# 6_Connector.net
KiCad netlist of a schematic drawn in Altium Designer
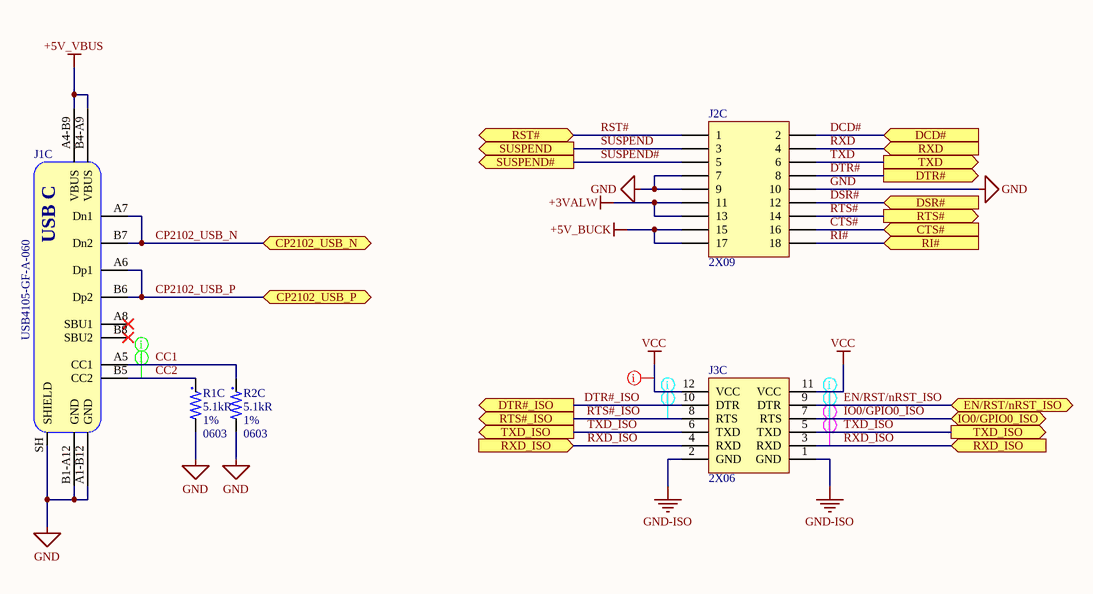
[diagram p0: 6_Connector.SchDoc]

(export (version "E")
  (design (tool "Eeschema 10.0.6"))
  (components
    (comp (ref "J1C")
      (value "USB4105-GF-A-060")
      (footprint "USB-Type-C-16-Pin-SMT")
      (description "USB Connector Type C SMT 16 Pin\r\n(Power pins joints = 12 pins)")
      (fields (field (name "MANUFACTURER") "GCT"))
      (libsource (lib "Lib_Connector") (part "USB-Type-C-16-Pin-SMT"))
    )
    (comp (ref "J2C")
      (value "2X09")
      (footprint "PinHeader_2x09_P2.54mm_Vertical")
      (libsource (lib "Lib_Connector_PinHeader_2.54mm") (part "PinHeader 2X09 DU"))
    )
    (comp (ref "J3C")
      (value "2X06")
      (footprint "PinHeader_2x06_P2.54mm_Vertical")
      (libsource (lib "Lib_Connector_PinHeader_2.54mm") (part "UART_2x06_P2.54mm_V2"))
    )
    (comp (ref "R1C")
      (value "5.1kR")
      (footprint "R0603-MFG")
      (description "SMD Chip Resistor, 5.1 kOhm, ± 1%, 100 mW, 0603 [1608 Metric], Thick Film, General Purpose")
      (fields
        (field (name "MANUFACTURER") "Vishay")
        (field (name "MANUFACTURER PART NUMBER") "CRCW06035K10FKEA")
        (field (name "TOLERANCE") "1%")
        (field (name "CASE/PACKAGE") "0603")
      )
      (libsource (lib "Lib_Register_0603") (part "5.1K"))
    )
    (comp (ref "R2C")
      (value "5.1kR")
      (footprint "R0603-MFG")
      (description "SMD Chip Resistor, 5.1 kOhm, ± 1%, 100 mW, 0603 [1608 Metric], Thick Film, General Purpose")
      (fields
        (field (name "MANUFACTURER") "Vishay")
        (field (name "MANUFACTURER PART NUMBER") "CRCW06035K10FKEA")
        (field (name "TOLERANCE") "1%")
        (field (name "CASE/PACKAGE") "0603")
      )
      (libsource (lib "Lib_Register_0603") (part "5.1K"))
    )
  )
  (nets
    (net (code "1") (name "+3VALW") (class "Default")
      (node (ref "J2C") (pin "11") (pinfunction "11_11") (pintype "passive"))
      (node (ref "J2C") (pin "13") (pinfunction "13_13") (pintype "passive"))
    )
    (net (code "2") (name "+5V_BUCK") (class "Default")
      (node (ref "J2C") (pin "15") (pinfunction "15_15") (pintype "passive"))
      (node (ref "J2C") (pin "17") (pinfunction "17_17") (pintype "passive"))
    )
    (net (code "3") (name "+5V_VBUS") (class "Default")
      (node (ref "J1C") (pin "A4-B9") (pinfunction "VBUS_A4-B9") (pintype "passive"))
      (node (ref "J1C") (pin "B4-A9") (pinfunction "VBUS_B4-A9") (pintype "passive"))
    )
    (net (code "4") (name "/CC1") (class "Default")
      (node (ref "J1C") (pin "A5") (pinfunction "CC1_A5") (pintype "passive"))
      (node (ref "R2C") (pin "1") (pinfunction "1_1") (pintype "passive"))
    )
    (net (code "5") (name "/CC2") (class "Default")
      (node (ref "J1C") (pin "B5") (pinfunction "CC2_B5") (pintype "passive"))
      (node (ref "R1C") (pin "1") (pinfunction "1_1") (pintype "passive"))
    )
    (net (code "6") (name "/CP2102_USB_N") (class "Default")
      (node (ref "J1C") (pin "A7") (pinfunction "Dn1_A7") (pintype "passive"))
      (node (ref "J1C") (pin "B7") (pinfunction "Dn2_B7") (pintype "passive"))
    )
    (net (code "7") (name "/CP2102_USB_P") (class "Default")
      (node (ref "J1C") (pin "A6") (pinfunction "Dp1_A6") (pintype "passive"))
      (node (ref "J1C") (pin "B6") (pinfunction "Dp2_B6") (pintype "passive"))
    )
    (net (code "8") (name "/CTS#") (class "Default")
      (node (ref "J2C") (pin "16") (pinfunction "16_16") (pintype "passive"))
    )
    (net (code "9") (name "/DCD#") (class "Default")
      (node (ref "J2C") (pin "2") (pinfunction "2_2") (pintype "passive"))
    )
    (net (code "10") (name "/DSR#") (class "Default")
      (node (ref "J2C") (pin "12") (pinfunction "12_12") (pintype "passive"))
    )
    (net (code "11") (name "/DTR#") (class "Default")
      (node (ref "J2C") (pin "8") (pinfunction "8_8") (pintype "passive"))
    )
    (net (code "12") (name "/DTR#_ISO") (class "Default")
      (node (ref "J3C") (pin "10") (pinfunction "DTR_10") (pintype "passive"))
    )
    (net (code "13") (name "/EN{slash}RST{slash}nRST_ISO") (class "Default")
      (node (ref "J3C") (pin "9") (pinfunction "DTR_9") (pintype "passive"))
    )
    (net (code "14") (name "/IO0{slash}GPIO0_ISO") (class "Default")
      (node (ref "J3C") (pin "7") (pinfunction "RTS_7") (pintype "passive"))
    )
    (net (code "15") (name "/RI#") (class "Default")
      (node (ref "J2C") (pin "18") (pinfunction "18_18") (pintype "passive"))
    )
    (net (code "16") (name "/RST#") (class "Default")
      (node (ref "J2C") (pin "1") (pinfunction "1_1") (pintype "passive"))
    )
    (net (code "17") (name "/RTS#") (class "Default")
      (node (ref "J2C") (pin "14") (pinfunction "14_14") (pintype "passive"))
    )
    (net (code "18") (name "/RTS#_ISO") (class "Default")
      (node (ref "J3C") (pin "8") (pinfunction "RTS_8") (pintype "passive"))
    )
    (net (code "19") (name "/RXD") (class "Default")
      (node (ref "J2C") (pin "4") (pinfunction "4_4") (pintype "passive"))
    )
    (net (code "20") (name "/RXD_ISO") (class "Default")
      (node (ref "J3C") (pin "3") (pinfunction "RXD_3") (pintype "passive"))
      (node (ref "J3C") (pin "4") (pinfunction "RXD_4") (pintype "passive"))
    )
    (net (code "21") (name "/SUSPEND") (class "Default")
      (node (ref "J2C") (pin "3") (pinfunction "3_3") (pintype "passive"))
    )
    (net (code "22") (name "/SUSPEND#") (class "Default")
      (node (ref "J2C") (pin "5") (pinfunction "5_5") (pintype "passive"))
    )
    (net (code "23") (name "/TXD") (class "Default")
      (node (ref "J2C") (pin "6") (pinfunction "6_6") (pintype "passive"))
    )
    (net (code "24") (name "/TXD_ISO") (class "Default")
      (node (ref "J3C") (pin "5") (pinfunction "TXD_5") (pintype "passive"))
      (node (ref "J3C") (pin "6") (pinfunction "TXD_6") (pintype "passive"))
    )
    (net (code "25") (name "GND") (class "Default")
      (node (ref "J1C") (pin "A1-B12") (pinfunction "GND_A1-B12") (pintype "passive"))
      (node (ref "J1C") (pin "B1-A12") (pinfunction "GND_B1-A12") (pintype "passive"))
      (node (ref "J1C") (pin "SH") (pinfunction "SHIELD_SH") (pintype "passive"))
      (node (ref "J2C") (pin "10") (pinfunction "10_10") (pintype "passive"))
      (node (ref "J2C") (pin "7") (pinfunction "7_7") (pintype "passive"))
      (node (ref "J2C") (pin "9") (pinfunction "9_9") (pintype "passive"))
      (node (ref "R1C") (pin "2") (pinfunction "2_2") (pintype "passive"))
      (node (ref "R2C") (pin "2") (pinfunction "2_2") (pintype "passive"))
    )
    (net (code "26") (name "GND-ISO") (class "Default")
      (node (ref "J3C") (pin "1") (pinfunction "GND_1") (pintype "passive"))
      (node (ref "J3C") (pin "2") (pinfunction "GND_2") (pintype "passive"))
    )
    (net (code "27") (name "VCC") (class "Default")
      (node (ref "J3C") (pin "11") (pinfunction "VCC_11") (pintype "passive"))
      (node (ref "J3C") (pin "12") (pinfunction "VCC_12") (pintype "passive"))
    )
    (net (code "28") (name "unconnected-(J1C-SBU1-PadA8)") (class "Default")
      (node (ref "J1C") (pin "A8") (pinfunction "SBU1_A8") (pintype "passive+no_connect"))
    )
    (net (code "29") (name "unconnected-(J1C-SBU2-PadB8)") (class "Default")
      (node (ref "J1C") (pin "B8") (pinfunction "SBU2_B8") (pintype "passive+no_connect"))
    )
  )
)
